# booster_2_01_32U4.net
KiCad netlist of a schematic drawn in EAGLE
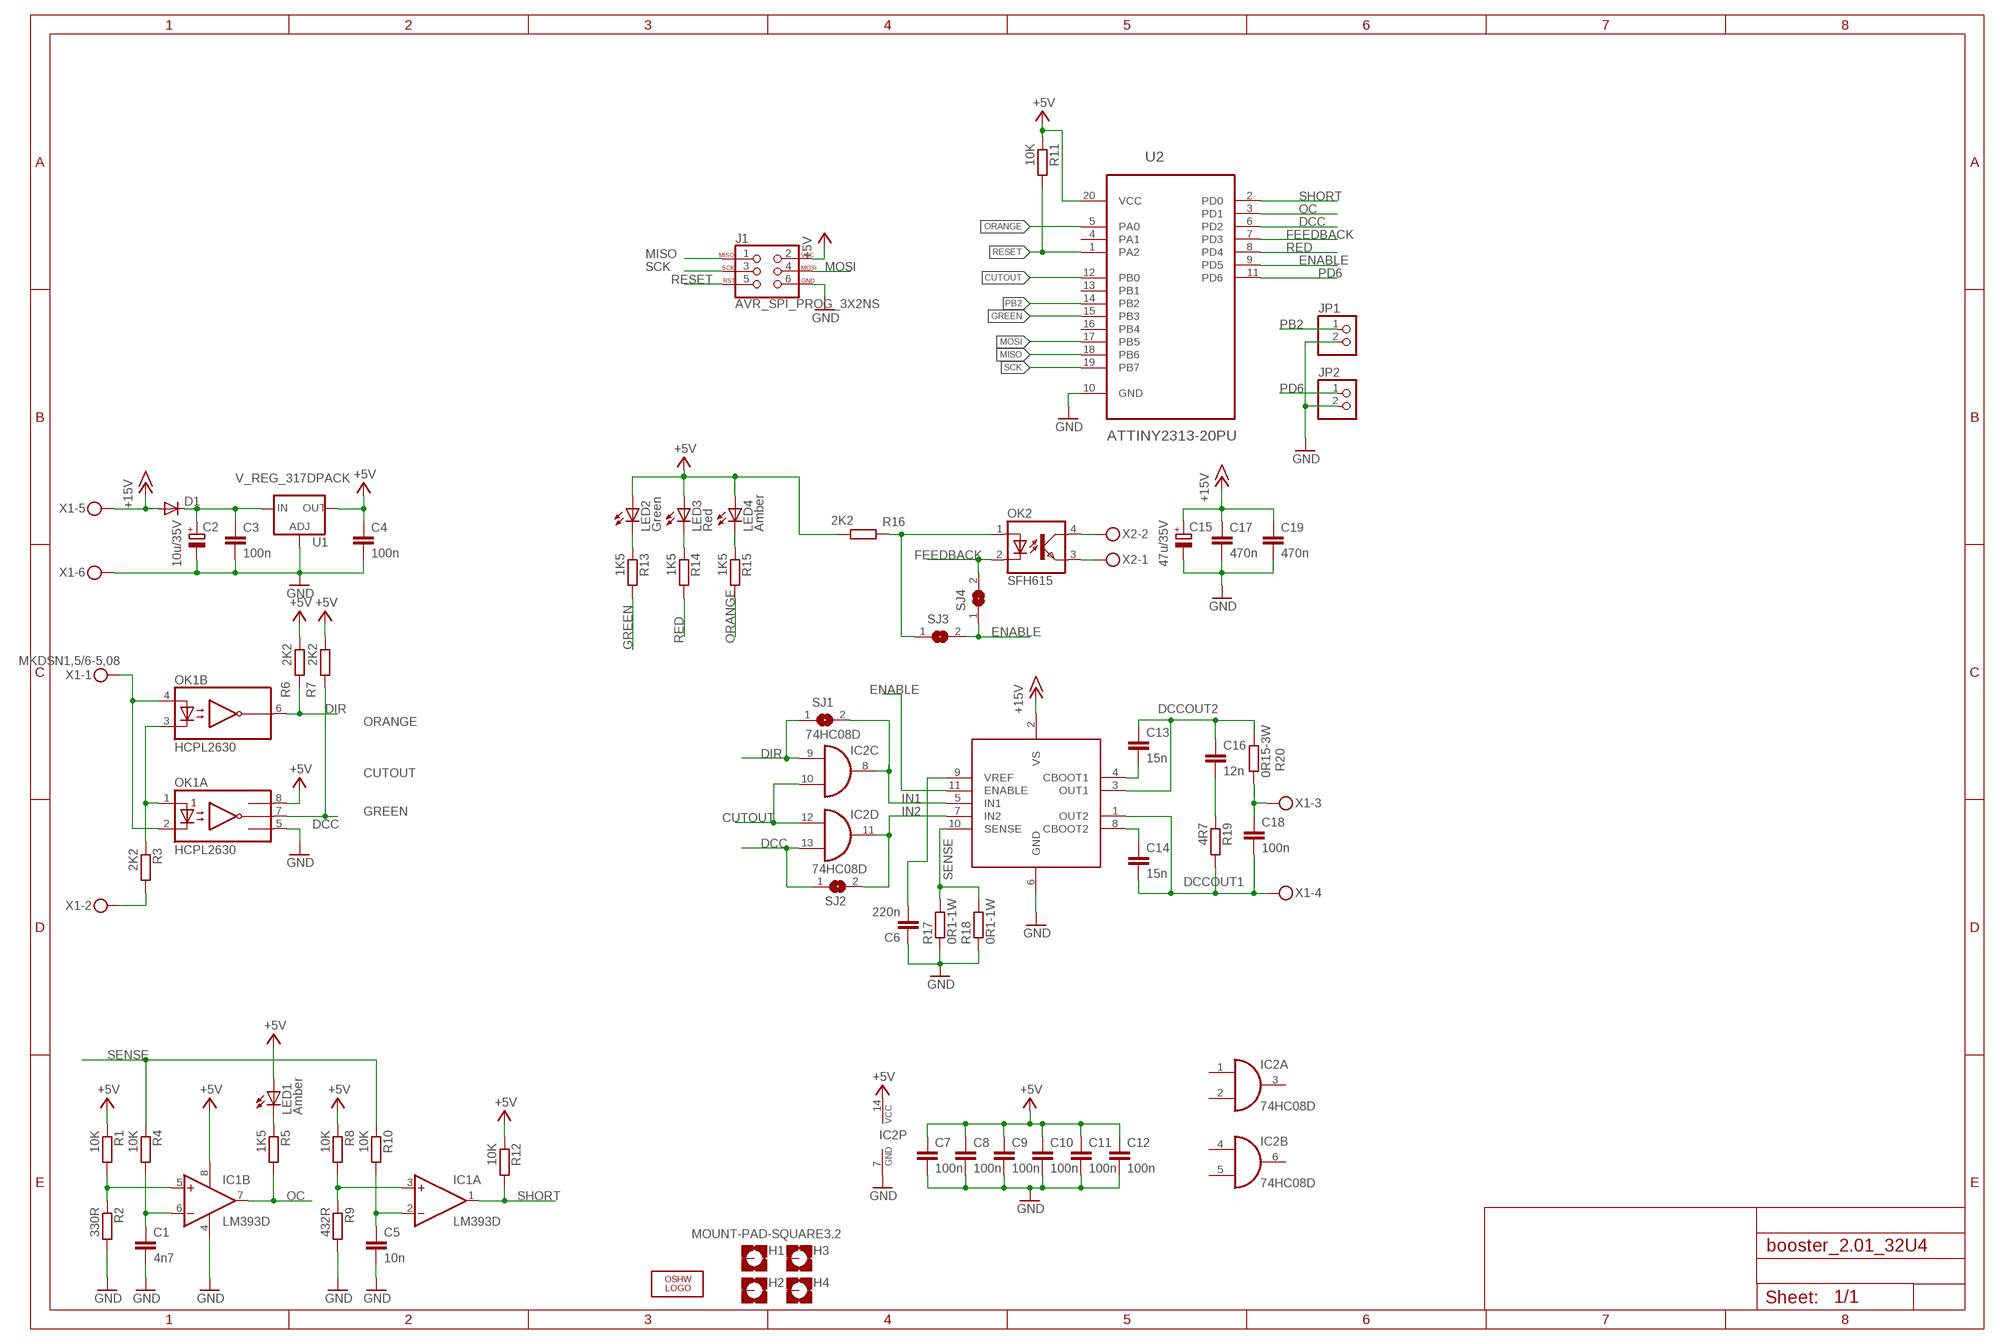
[diagram p0: schematic, sheet 1]

(export (version "E")
  (design (tool "Eeschema 10.0.6"))
  (components
    (comp (ref "C1")
      (value "4n7")
      (footprint "eagle-import:C0805")
      (libsource (lib "eagle-import") (part "C-EUC0805"))
    )
    (comp (ref "C2")
      (value "10u/35V")
      (footprint "eagle-import:E2,5-5")
      (libsource (lib "eagle-import") (part "CPOL-EUE2.5-5"))
    )
    (comp (ref "C3")
      (value "100n")
      (footprint "eagle-import:C0805")
      (libsource (lib "eagle-import") (part "C-EUC0805"))
    )
    (comp (ref "C4")
      (value "100n")
      (footprint "eagle-import:C0805")
      (libsource (lib "eagle-import") (part "C-EUC0805"))
    )
    (comp (ref "C5")
      (value "10n")
      (footprint "eagle-import:C0805")
      (libsource (lib "eagle-import") (part "C-EUC0805"))
    )
    (comp (ref "C6")
      (value "220n")
      (footprint "eagle-import:C0805")
      (libsource (lib "eagle-import") (part "C-EUC0805"))
    )
    (comp (ref "C7")
      (value "100n")
      (footprint "eagle-import:C0805")
      (libsource (lib "eagle-import") (part "C-EUC0805"))
    )
    (comp (ref "C8")
      (value "100n")
      (footprint "eagle-import:C0805")
      (libsource (lib "eagle-import") (part "C-EUC0805"))
    )
    (comp (ref "C9")
      (value "100n")
      (footprint "eagle-import:C0805")
      (libsource (lib "eagle-import") (part "C-EUC0805"))
    )
    (comp (ref "C10")
      (value "100n")
      (footprint "eagle-import:C0805")
      (libsource (lib "eagle-import") (part "C-EUC0805"))
    )
    (comp (ref "C11")
      (value "100n")
      (footprint "eagle-import:C0805")
      (libsource (lib "eagle-import") (part "C-EUC0805"))
    )
    (comp (ref "C12")
      (value "100n")
      (footprint "eagle-import:C0805")
      (libsource (lib "eagle-import") (part "C-EUC0805"))
    )
    (comp (ref "C13")
      (value "15n")
      (footprint "eagle-import:C0805")
      (libsource (lib "eagle-import") (part "C-EUC0805"))
    )
    (comp (ref "C14")
      (value "15n")
      (footprint "eagle-import:C0805")
      (libsource (lib "eagle-import") (part "C-EUC0805"))
    )
    (comp (ref "C15")
      (value "47u/35V")
      (footprint "eagle-import:E2,5-5")
      (libsource (lib "eagle-import") (part "CPOL-EUE2.5-5"))
    )
    (comp (ref "C16")
      (value "12n")
      (footprint "eagle-import:C0805")
      (libsource (lib "eagle-import") (part "C-EUC0805"))
    )
    (comp (ref "C17")
      (value "470n")
      (footprint "eagle-import:C1812")
      (libsource (lib "eagle-import") (part "rcl_334_C-EUC1812"))
    )
    (comp (ref "C18")
      (value "100n")
      (footprint "eagle-import:C0805")
      (libsource (lib "eagle-import") (part "C-EUC0805"))
    )
    (comp (ref "C19")
      (value "470n")
      (footprint "eagle-import:C1812")
      (libsource (lib "eagle-import") (part "rcl_334_C-EUC1812"))
    )
    (comp (ref "D1")
      (value "DIODE-SMB")
      (footprint "eagle-import:SMB")
      (libsource (lib "eagle-import") (part "DIODE-SMB"))
    )
    (comp (ref "H1")
      (value "MOUNT-PAD-SQUARE3.2")
      (footprint "eagle-import:3,2-PAD-SQUARE")
      (libsource (lib "eagle-import") (part "MOUNT-PAD-SQUARE3.2"))
    )
    (comp (ref "H2")
      (value "MOUNT-PAD-SQUARE3.2")
      (footprint "eagle-import:3,2-PAD-SQUARE")
      (libsource (lib "eagle-import") (part "MOUNT-PAD-SQUARE3.2"))
    )
    (comp (ref "H3")
      (value "MOUNT-PAD-SQUARE3.2")
      (footprint "eagle-import:3,2-PAD-SQUARE")
      (libsource (lib "eagle-import") (part "MOUNT-PAD-SQUARE3.2"))
    )
    (comp (ref "H4")
      (value "MOUNT-PAD-SQUARE3.2")
      (footprint "eagle-import:3,2-PAD-SQUARE")
      (libsource (lib "eagle-import") (part "MOUNT-PAD-SQUARE3.2"))
    )
    (comp (ref "IC1")
      (value "LM393D")
      (footprint "eagle-import:SO08")
      (libsource (lib "eagle-import") (part "LM393D"))
    )
    (comp (ref "IC2")
      (value "74HC08D")
      (footprint "eagle-import:SO14")
      (libsource (lib "eagle-import") (part "7408DHC"))
    )
    (comp (ref "J1")
      (value "AVR_SPI_PROG_3X2NS")
      (footprint "eagle-import:2X3-NS")
      (libsource (lib "eagle-import") (part "AVR_SPI_PROG_3X2NS"))
    )
    (comp (ref "JP1")
      (value "PINHD-1X2")
      (footprint "eagle-import:1X02")
      (libsource (lib "eagle-import") (part "PINHD-1X2"))
    )
    (comp (ref "JP2")
      (value "PINHD-1X2")
      (footprint "eagle-import:1X02")
      (libsource (lib "eagle-import") (part "PINHD-1X2"))
    )
    (comp (ref "LED1")
      (value "Amber")
      (footprint "eagle-import:LED3MM")
      (libsource (lib "eagle-import") (part "LED3MM"))
    )
    (comp (ref "LED2")
      (value "Green")
      (footprint "eagle-import:LED3MM")
      (libsource (lib "eagle-import") (part "LED3MM"))
    )
    (comp (ref "LED3")
      (value "Red")
      (footprint "eagle-import:LED3MM")
      (libsource (lib "eagle-import") (part "LED3MM"))
    )
    (comp (ref "LED4")
      (value "Amber")
      (footprint "eagle-import:LED3MM")
      (libsource (lib "eagle-import") (part "LED3MM"))
    )
    (comp (ref "LOGO1")
      (value "OSHW_LOGO_6MILX0200-NT")
      (footprint "eagle-import:OSHW_6X200_NOTEXT")
      (libsource (lib "eagle-import") (part "OSHW_LOGO_6MILX0200-NT"))
    )
    (comp (ref "OK1")
      (value "HCPL2630")
      (footprint "eagle-import:DIL08")
      (fields (field (name "MF") "AGILENT TECHNOLOGIES") (field (name "MPN") "HCPL-2630-000E"))
      (libsource (lib "eagle-import") (part "HCPL2630"))
    )
    (comp (ref "OK2")
      (value "SFH615")
      (footprint "eagle-import:DIL04")
      (fields (field (name "MPN") "SFH615A-2"))
      (libsource (lib "eagle-import") (part "SFH615"))
    )
    (comp (ref "R1")
      (value "10K")
      (footprint "eagle-import:R0805")
      (libsource (lib "eagle-import") (part "R-EU_R0805"))
    )
    (comp (ref "R2")
      (value "330R")
      (footprint "eagle-import:R0805")
      (libsource (lib "eagle-import") (part "R-EU_R0805"))
    )
    (comp (ref "R3")
      (value "2K2")
      (footprint "eagle-import:R0805")
      (libsource (lib "eagle-import") (part "R-EU_R0805"))
    )
    (comp (ref "R4")
      (value "10K")
      (footprint "eagle-import:R0805")
      (libsource (lib "eagle-import") (part "R-EU_R0805"))
    )
    (comp (ref "R5")
      (value "1K5")
      (footprint "eagle-import:R0805")
      (libsource (lib "eagle-import") (part "R-EU_R0805"))
    )
    (comp (ref "R6")
      (value "2K2")
      (footprint "eagle-import:R0805")
      (libsource (lib "eagle-import") (part "R-EU_R0805"))
    )
    (comp (ref "R7")
      (value "2K2")
      (footprint "eagle-import:R0805")
      (libsource (lib "eagle-import") (part "R-EU_R0805"))
    )
    (comp (ref "R8")
      (value "10K")
      (footprint "eagle-import:R0805")
      (libsource (lib "eagle-import") (part "R-EU_R0805"))
    )
    (comp (ref "R9")
      (value "432R")
      (footprint "eagle-import:R0805")
      (libsource (lib "eagle-import") (part "R-EU_R0805"))
    )
    (comp (ref "R10")
      (value "10K")
      (footprint "eagle-import:R0805")
      (libsource (lib "eagle-import") (part "R-EU_R0805"))
    )
    (comp (ref "R11")
      (value "10K")
      (footprint "eagle-import:R0805")
      (libsource (lib "eagle-import") (part "R-EU_R0805"))
    )
    (comp (ref "R12")
      (value "10K")
      (footprint "eagle-import:R0805")
      (libsource (lib "eagle-import") (part "R-EU_R0805"))
    )
    (comp (ref "R13")
      (value "1K5")
      (footprint "eagle-import:R0805")
      (libsource (lib "eagle-import") (part "R-EU_R0805"))
    )
    (comp (ref "R14")
      (value "1K5")
      (footprint "eagle-import:R0805")
      (libsource (lib "eagle-import") (part "R-EU_R0805"))
    )
    (comp (ref "R15")
      (value "1K5")
      (footprint "eagle-import:R0805")
      (libsource (lib "eagle-import") (part "R-EU_R0805"))
    )
    (comp (ref "R16")
      (value "2K2")
      (footprint "eagle-import:R0805")
      (libsource (lib "eagle-import") (part "R-EU_R0805"))
    )
    (comp (ref "R17")
      (value "0R1-1W")
      (footprint "eagle-import:R2512")
      (libsource (lib "eagle-import") (part "rcl_334_R-EU_R2512"))
    )
    (comp (ref "R18")
      (value "0R1-1W")
      (footprint "eagle-import:R2512")
      (libsource (lib "eagle-import") (part "rcl_334_R-EU_R2512"))
    )
    (comp (ref "R19")
      (value "4R7")
      (footprint "eagle-import:R0805")
      (libsource (lib "eagle-import") (part "R-EU_R0805"))
    )
    (comp (ref "R20")
      (value "0R15-3W")
      (footprint "eagle-import:P0817V")
      (libsource (lib "eagle-import") (part "rcl_334_R-EU_0817/7V"))
    )
    (comp (ref "SJ1") (value "SJ") (footprint "eagle-import:SJ") (libsource (lib "eagle-import") (part "SJ")))
    (comp (ref "SJ2") (value "SJ") (footprint "eagle-import:SJ") (libsource (lib "eagle-import") (part "SJ")))
    (comp (ref "SJ3") (value "SJ") (footprint "eagle-import:SJ") (libsource (lib "eagle-import") (part "SJ")))
    (comp (ref "SJ4") (value "SJ") (footprint "eagle-import:SJ") (libsource (lib "eagle-import") (part "SJ")))
    (comp (ref "U1")
      (value "V_REG_317DPACK")
      (footprint "eagle-import:V-REG_DPACK")
      (libsource (lib "eagle-import") (part "V_REG_317DPACK"))
    )
    (comp (ref "U2")
      (value "ATTINY2313-20PU")
      (footprint "eagle-import:DIP254P762X533-20")
      (libsource (lib "eagle-import") (part "ATTINY2313-20PU"))
    )
    (comp (ref "U3")
      (value "L6203")
      (footprint "eagle-import:ZIP_11")
      (fields (field (name "MANUFACTURER") "STM"))
      (libsource (lib "eagle-import") (part "L6203"))
    )
    (comp (ref "X1")
      (value "MKDSN1,5/6-5,08")
      (footprint "eagle-import:MKDSN1,5_6-5,08")
      (libsource (lib "eagle-import") (part "MKDSN1,5/6-5,08"))
    )
    (comp (ref "X2")
      (value "MKDSN1,5/2-5,08")
      (footprint "eagle-import:MKDSN1,5_2-5,08")
      (libsource (lib "eagle-import") (part "MKDSN1,5/2-5,08"))
    )
  )
  (nets
    (net (code "1") (name "+5V") (class "Default")
      (node (ref "C10") (pin "1") (pinfunction "1_1") (pintype "passive"))
      (node (ref "C11") (pin "1") (pinfunction "1_1") (pintype "passive"))
      (node (ref "C12") (pin "1") (pinfunction "1_1") (pintype "passive"))
      (node (ref "C4") (pin "1") (pinfunction "1_1") (pintype "passive"))
      (node (ref "C7") (pin "1") (pinfunction "1_1") (pintype "passive"))
      (node (ref "C8") (pin "1") (pinfunction "1_1") (pintype "passive"))
      (node (ref "C9") (pin "1") (pinfunction "1_1") (pintype "passive"))
      (node (ref "IC1") (pin "8") (pinfunction "V+_8") (pintype "power_in"))
      (node (ref "IC2") (pin "14") (pinfunction "VCC_14") (pintype "power_in"))
      (node (ref "J1") (pin "2") (pinfunction "2_2") (pintype "passive"))
      (node (ref "LED1") (pin "A") (pinfunction "A_A") (pintype "passive"))
      (node (ref "LED2") (pin "A") (pinfunction "A_A") (pintype "passive"))
      (node (ref "LED3") (pin "A") (pinfunction "A_A") (pintype "passive"))
      (node (ref "LED4") (pin "A") (pinfunction "A_A") (pintype "passive"))
      (node (ref "OK1") (pin "8") (pinfunction "VCC_8") (pintype "passive"))
      (node (ref "R1") (pin "1") (pinfunction "1_1") (pintype "passive"))
      (node (ref "R11") (pin "1") (pinfunction "1_1") (pintype "passive"))
      (node (ref "R12") (pin "1") (pinfunction "1_1") (pintype "passive"))
      (node (ref "R16") (pin "1") (pinfunction "1_1") (pintype "passive"))
      (node (ref "R6") (pin "1") (pinfunction "1_1") (pintype "passive"))
      (node (ref "R7") (pin "1") (pinfunction "1_1") (pintype "passive"))
      (node (ref "R8") (pin "1") (pinfunction "1_1") (pintype "passive"))
      (node (ref "U1") (pin "4") (pinfunction "OUT_4") (pintype "output"))
      (node (ref "U2") (pin "20") (pinfunction "VCC_20") (pintype "power_in"))
    )
    (net (code "2") (name "+15V") (class "Default")
      (node (ref "C15") (pin "+") (pinfunction "+_+") (pintype "passive"))
      (node (ref "C17") (pin "1") (pinfunction "1_1") (pintype "passive"))
      (node (ref "C19") (pin "1") (pinfunction "1_1") (pintype "passive"))
      (node (ref "D1") (pin "A") (pinfunction "A_A") (pintype "passive"))
      (node (ref "U3") (pin "2") (pinfunction "VS_2") (pintype "power_in"))
      (node (ref "X1") (pin "5") (pinfunction "KL_5") (pintype "passive"))
    )
    (net (code "3") (name "/DCC") (class "Default")
      (node (ref "IC2") (pin "13") (pinfunction "I1_13") (pintype "input"))
      (node (ref "OK1") (pin "7") (pinfunction "VO1_7") (pintype "passive"))
      (node (ref "R7") (pin "2") (pinfunction "2_2") (pintype "passive"))
      (node (ref "SJ2") (pin "1") (pinfunction "1_1") (pintype "passive"))
      (node (ref "U2") (pin "6") (pinfunction "PD2_6") (pintype "bidirectional"))
    )
    (net (code "4") (name "/DCCOUT1") (class "Default")
      (node (ref "C14") (pin "2") (pinfunction "2_2") (pintype "passive"))
      (node (ref "C18") (pin "2") (pinfunction "2_2") (pintype "passive"))
      (node (ref "R19") (pin "2") (pinfunction "2_2") (pintype "passive"))
      (node (ref "U3") (pin "1") (pinfunction "OUT2_1") (pintype "output"))
      (node (ref "X1") (pin "4") (pinfunction "KL_4") (pintype "passive"))
    )
    (net (code "5") (name "/DCCOUT2") (class "Default")
      (node (ref "C13") (pin "1") (pinfunction "1_1") (pintype "passive"))
      (node (ref "C16") (pin "1") (pinfunction "1_1") (pintype "passive"))
      (node (ref "R20") (pin "2") (pinfunction "2_2") (pintype "passive"))
      (node (ref "U3") (pin "3") (pinfunction "OUT1_3") (pintype "output"))
    )
    (net (code "6") (name "/DIR") (class "Default")
      (node (ref "IC2") (pin "9") (pinfunction "I0_9") (pintype "input"))
      (node (ref "OK1") (pin "6") (pinfunction "VO2_6") (pintype "passive"))
      (node (ref "R6") (pin "2") (pinfunction "2_2") (pintype "passive"))
      (node (ref "SJ1") (pin "1") (pinfunction "1_1") (pintype "passive"))
    )
    (net (code "7") (name "/ENABLE") (class "Default")
      (node (ref "SJ3") (pin "2") (pinfunction "2_2") (pintype "passive"))
      (node (ref "SJ4") (pin "1") (pinfunction "1_1") (pintype "passive"))
      (node (ref "U2") (pin "9") (pinfunction "PD5_9") (pintype "bidirectional"))
      (node (ref "U3") (pin "11") (pinfunction "ENABLE_11") (pintype "input"))
    )
    (net (code "8") (name "/FEEDBACK") (class "Default")
      (node (ref "OK2") (pin "2") (pinfunction "C_2") (pintype "passive"))
      (node (ref "SJ4") (pin "2") (pinfunction "2_2") (pintype "passive"))
      (node (ref "U2") (pin "7") (pinfunction "PD3_7") (pintype "bidirectional"))
    )
    (net (code "9") (name "/IN1") (class "Default")
      (node (ref "IC2") (pin "8") (pinfunction "O_8") (pintype "output"))
      (node (ref "SJ1") (pin "2") (pinfunction "2_2") (pintype "passive"))
      (node (ref "U3") (pin "5") (pinfunction "IN1_5") (pintype "input"))
    )
    (net (code "10") (name "/IN2") (class "Default")
      (node (ref "IC2") (pin "11") (pinfunction "O_11") (pintype "output"))
      (node (ref "SJ2") (pin "2") (pinfunction "2_2") (pintype "passive"))
      (node (ref "U3") (pin "7") (pinfunction "IN2_7") (pintype "input"))
    )
    (net (code "11") (name "/OC") (class "Default")
      (node (ref "IC1") (pin "7") (pinfunction "OUT_7") (pintype "output"))
      (node (ref "R5") (pin "2") (pinfunction "2_2") (pintype "passive"))
      (node (ref "U2") (pin "3") (pinfunction "PD1_3") (pintype "bidirectional"))
    )
    (net (code "12") (name "/PD6") (class "Default")
      (node (ref "JP2") (pin "1") (pinfunction "1_1") (pintype "passive"))
      (node (ref "U2") (pin "11") (pinfunction "PD6_11") (pintype "bidirectional"))
    )
    (net (code "13") (name "/RED") (class "Default")
      (node (ref "R14") (pin "2") (pinfunction "2_2") (pintype "passive"))
      (node (ref "U2") (pin "8") (pinfunction "PD4_8") (pintype "bidirectional"))
    )
    (net (code "14") (name "/SENSE") (class "Default")
      (node (ref "R10") (pin "1") (pinfunction "1_1") (pintype "passive"))
      (node (ref "R17") (pin "2") (pinfunction "2_2") (pintype "passive"))
      (node (ref "R18") (pin "2") (pinfunction "2_2") (pintype "passive"))
      (node (ref "R4") (pin "1") (pinfunction "1_1") (pintype "passive"))
      (node (ref "U3") (pin "10") (pinfunction "SENSE_10") (pintype "input"))
    )
    (net (code "15") (name "/SHORT") (class "Default")
      (node (ref "IC1") (pin "1") (pinfunction "OUT_1") (pintype "output"))
      (node (ref "R12") (pin "2") (pinfunction "2_2") (pintype "passive"))
      (node (ref "U2") (pin "2") (pinfunction "PD0_2") (pintype "bidirectional"))
    )
    (net (code "16") (name "CUTOUT") (class "Default")
      (node (ref "IC2") (pin "10") (pinfunction "I1_10") (pintype "input"))
      (node (ref "IC2") (pin "12") (pinfunction "I0_12") (pintype "input"))
      (node (ref "U2") (pin "12") (pinfunction "PB0_12") (pintype "bidirectional"))
    )
    (net (code "17") (name "GND") (class "Default")
      (node (ref "C1") (pin "2") (pinfunction "2_2") (pintype "passive"))
      (node (ref "C10") (pin "2") (pinfunction "2_2") (pintype "passive"))
      (node (ref "C11") (pin "2") (pinfunction "2_2") (pintype "passive"))
      (node (ref "C12") (pin "2") (pinfunction "2_2") (pintype "passive"))
      (node (ref "C15") (pin "-") (pinfunction "-_-") (pintype "passive"))
      (node (ref "C17") (pin "2") (pinfunction "2_2") (pintype "passive"))
      (node (ref "C19") (pin "2") (pinfunction "2_2") (pintype "passive"))
      (node (ref "C2") (pin "-") (pinfunction "-_-") (pintype "passive"))
      (node (ref "C3") (pin "2") (pinfunction "2_2") (pintype "passive"))
      (node (ref "C4") (pin "2") (pinfunction "2_2") (pintype "passive"))
      (node (ref "C5") (pin "2") (pinfunction "2_2") (pintype "passive"))
      (node (ref "C6") (pin "1") (pinfunction "1_1") (pintype "passive"))
      (node (ref "C7") (pin "2") (pinfunction "2_2") (pintype "passive"))
      (node (ref "C8") (pin "2") (pinfunction "2_2") (pintype "passive"))
      (node (ref "C9") (pin "2") (pinfunction "2_2") (pintype "passive"))
      (node (ref "IC1") (pin "4") (pinfunction "V-_4") (pintype "power_in"))
      (node (ref "IC2") (pin "7") (pinfunction "GND_7") (pintype "power_in"))
      (node (ref "J1") (pin "6") (pinfunction "6_6") (pintype "passive"))
      (node (ref "JP1") (pin "2") (pinfunction "2_2") (pintype "passive"))
      (node (ref "JP2") (pin "2") (pinfunction "2_2") (pintype "passive"))
      (node (ref "OK1") (pin "5") (pinfunction "GND_5") (pintype "passive"))
      (node (ref "R17") (pin "1") (pinfunction "1_1") (pintype "passive"))
      (node (ref "R18") (pin "1") (pinfunction "1_1") (pintype "passive"))
      (node (ref "R2") (pin "2") (pinfunction "2_2") (pintype "passive"))
      (node (ref "R9") (pin "2") (pinfunction "2_2") (pintype "passive"))
      (node (ref "U1") (pin "1") (pinfunction "ADJ_1") (pintype "input"))
      (node (ref "U2") (pin "10") (pinfunction "GND_10") (pintype "passive"))
      (node (ref "U3") (pin "6") (pinfunction "GND_6") (pintype "passive"))
      (node (ref "X1") (pin "6") (pinfunction "KL_6") (pintype "passive"))
    )
    (net (code "18") (name "GREEN") (class "Default")
      (node (ref "R13") (pin "2") (pinfunction "2_2") (pintype "passive"))
      (node (ref "U2") (pin "15") (pinfunction "PB3_15") (pintype "bidirectional"))
    )
    (net (code "19") (name "MISO") (class "Default")
      (node (ref "J1") (pin "1") (pinfunction "1_1") (pintype "passive"))
      (node (ref "U2") (pin "18") (pinfunction "PB6_18") (pintype "bidirectional"))
    )
    (net (code "20") (name "MOSI") (class "Default")
      (node (ref "J1") (pin "4") (pinfunction "4_4") (pintype "passive"))
      (node (ref "U2") (pin "17") (pinfunction "PB5_17") (pintype "bidirectional"))
    )
    (net (code "21") (name "Net-(C16-Pad2)") (class "Default")
      (node (ref "C16") (pin "2") (pinfunction "2_2") (pintype "passive"))
      (node (ref "R19") (pin "1") (pinfunction "1_1") (pintype "passive"))
    )
    (net (code "22") (name "Net-(IC1A-+IN)") (class "Default")
      (node (ref "IC1") (pin "3") (pinfunction "+IN_3") (pintype "input"))
      (node (ref "R8") (pin "2") (pinfunction "2_2") (pintype "passive"))
      (node (ref "R9") (pin "1") (pinfunction "1_1") (pintype "passive"))
    )
    (net (code "23") (name "Net-(IC1A--IN)") (class "Default")
      (node (ref "C5") (pin "1") (pinfunction "1_1") (pintype "passive"))
      (node (ref "IC1") (pin "2") (pinfunction "-IN_2") (pintype "input"))
      (node (ref "R10") (pin "2") (pinfunction "2_2") (pintype "passive"))
    )
    (net (code "24") (name "Net-(IC1B-+IN)") (class "Default")
      (node (ref "IC1") (pin "5") (pinfunction "+IN_5") (pintype "input"))
      (node (ref "R1") (pin "2") (pinfunction "2_2") (pintype "passive"))
      (node (ref "R2") (pin "1") (pinfunction "1_1") (pintype "passive"))
    )
    (net (code "25") (name "Net-(IC1B--IN)") (class "Default")
      (node (ref "C1") (pin "1") (pinfunction "1_1") (pintype "passive"))
      (node (ref "IC1") (pin "6") (pinfunction "-IN_6") (pintype "input"))
      (node (ref "R4") (pin "2") (pinfunction "2_2") (pintype "passive"))
    )
    (net (code "26") (name "Net-(LED1-C)") (class "Default")
      (node (ref "LED1") (pin "K") (pinfunction "C_K") (pintype "passive"))
      (node (ref "R5") (pin "1") (pinfunction "1_1") (pintype "passive"))
    )
    (net (code "27") (name "Net-(LED2-C)") (class "Default")
      (node (ref "LED2") (pin "K") (pinfunction "C_K") (pintype "passive"))
      (node (ref "R13") (pin "1") (pinfunction "1_1") (pintype "passive"))
    )
    (net (code "28") (name "Net-(LED3-C)") (class "Default")
      (node (ref "LED3") (pin "K") (pinfunction "C_K") (pintype "passive"))
      (node (ref "R14") (pin "1") (pinfunction "1_1") (pintype "passive"))
    )
    (net (code "29") (name "Net-(LED4-C)") (class "Default")
      (node (ref "LED4") (pin "K") (pinfunction "C_K") (pintype "passive"))
      (node (ref "R15") (pin "1") (pinfunction "1_1") (pintype "passive"))
    )
    (net (code "30") (name "Net-(OK1A-A1)") (class "Default")
      (node (ref "OK1") (pin "1") (pinfunction "A1_1") (pintype "passive"))
      (node (ref "OK1") (pin "3") (pinfunction "C2_3") (pintype "passive"))
      (node (ref "R3") (pin "1") (pinfunction "1_1") (pintype "passive"))
    )
    (net (code "31") (name "Net-(OK1A-C1)") (class "Default")
      (node (ref "OK1") (pin "2") (pinfunction "C1_2") (pintype "passive"))
      (node (ref "OK1") (pin "4") (pinfunction "A2_4") (pintype "passive"))
      (node (ref "X1") (pin "1") (pinfunction "KL_1") (pintype "passive"))
    )
    (net (code "32") (name "Net-(OK2-A)") (class "Default")
      (node (ref "OK2") (pin "1") (pinfunction "A_1") (pintype "passive"))
      (node (ref "R16") (pin "2") (pinfunction "2_2") (pintype "passive"))
      (node (ref "SJ3") (pin "1") (pinfunction "1_1") (pintype "passive"))
    )
    (net (code "33") (name "Net-(OK2-COL)") (class "Default")
      (node (ref "OK2") (pin "4") (pinfunction "COL_4") (pintype "passive"))
      (node (ref "X2") (pin "2") (pinfunction "KL_2") (pintype "passive"))
    )
    (net (code "34") (name "Net-(OK2-EMIT)") (class "Default")
      (node (ref "OK2") (pin "3") (pinfunction "EMIT_3") (pintype "passive"))
      (node (ref "X2") (pin "1") (pinfunction "KL_1") (pintype "passive"))
    )
    (net (code "35") (name "Net-(U1-IN)") (class "Default")
      (node (ref "C2") (pin "+") (pinfunction "+_+") (pintype "passive"))
      (node (ref "C3") (pin "1") (pinfunction "1_1") (pintype "passive"))
      (node (ref "D1") (pin "C") (pinfunction "C_C") (pintype "passive"))
      (node (ref "U1") (pin "3") (pinfunction "IN_3") (pintype "input"))
    )
    (net (code "36") (name "Net-(U3-CBOOT1)") (class "Default")
      (node (ref "C13") (pin "2") (pinfunction "2_2") (pintype "passive"))
      (node (ref "U3") (pin "4") (pinfunction "CBOOT1_4") (pintype "output"))
    )
    (net (code "37") (name "Net-(U3-CBOOT2)") (class "Default")
      (node (ref "C14") (pin "1") (pinfunction "1_1") (pintype "passive"))
      (node (ref "U3") (pin "8") (pinfunction "CBOOT2_8") (pintype "output"))
    )
    (net (code "38") (name "Net-(U3-VREF)") (class "Default")
      (node (ref "C6") (pin "2") (pinfunction "2_2") (pintype "passive"))
      (node (ref "U3") (pin "9") (pinfunction "VREF_9") (pintype "output"))
    )
    (net (code "39") (name "Net-(X1B-KL)") (class "Default")
      (node (ref "R3") (pin "2") (pinfunction "2_2") (pintype "passive"))
      (node (ref "X1") (pin "2") (pinfunction "KL_2") (pintype "passive"))
    )
    (net (code "40") (name "Net-(X1C-KL)") (class "Default")
      (node (ref "C18") (pin "1") (pinfunction "1_1") (pintype "passive"))
      (node (ref "R20") (pin "1") (pinfunction "1_1") (pintype "passive"))
      (node (ref "X1") (pin "3") (pinfunction "KL_3") (pintype "passive"))
    )
    (net (code "41") (name "ORANGE") (class "Default")
      (node (ref "R15") (pin "2") (pinfunction "2_2") (pintype "passive"))
      (node (ref "U2") (pin "5") (pinfunction "PA0_5") (pintype "bidirectional"))
    )
    (net (code "42") (name "PB2") (class "Default")
      (node (ref "JP1") (pin "1") (pinfunction "1_1") (pintype "passive"))
      (node (ref "U2") (pin "14") (pinfunction "PB2_14") (pintype "bidirectional"))
    )
    (net (code "43") (name "RESET") (class "Default")
      (node (ref "J1") (pin "5") (pinfunction "5_5") (pintype "passive"))
      (node (ref "R11") (pin "2") (pinfunction "2_2") (pintype "passive"))
      (node (ref "U2") (pin "1") (pinfunction "PA2_1") (pintype "bidirectional"))
    )
    (net (code "44") (name "SCK") (class "Default")
      (node (ref "J1") (pin "3") (pinfunction "3_3") (pintype "passive"))
      (node (ref "U2") (pin "19") (pinfunction "PB7_19") (pintype "bidirectional"))
    )
    (net (code "45") (name "unconnected-(H1-MOUNT-PadB3,2)") (class "Default")
      (node (ref "H1") (pin "B3,2") (pinfunction "MOUNT_B3,2") (pintype "passive"))
    )
    (net (code "46") (name "unconnected-(H2-MOUNT-PadB3,2)") (class "Default")
      (node (ref "H2") (pin "B3,2") (pinfunction "MOUNT_B3,2") (pintype "passive"))
    )
    (net (code "47") (name "unconnected-(H3-MOUNT-PadB3,2)") (class "Default")
      (node (ref "H3") (pin "B3,2") (pinfunction "MOUNT_B3,2") (pintype "passive"))
    )
    (net (code "48") (name "unconnected-(H4-MOUNT-PadB3,2)") (class "Default")
      (node (ref "H4") (pin "B3,2") (pinfunction "MOUNT_B3,2") (pintype "passive"))
    )
    (net (code "49") (name "unconnected-(IC2A-I0-Pad1)") (class "Default")
      (node (ref "IC2") (pin "1") (pinfunction "I0_1") (pintype "input"))
    )
    (net (code "50") (name "unconnected-(IC2A-I1-Pad2)") (class "Default")
      (node (ref "IC2") (pin "2") (pinfunction "I1_2") (pintype "input"))
    )
    (net (code "51") (name "unconnected-(IC2A-O-Pad3)") (class "Default")
      (node (ref "IC2") (pin "3") (pinfunction "O_3") (pintype "output"))
    )
    (net (code "52") (name "unconnected-(IC2B-I0-Pad4)") (class "Default")
      (node (ref "IC2") (pin "4") (pinfunction "I0_4") (pintype "input"))
    )
    (net (code "53") (name "unconnected-(IC2B-I1-Pad5)") (class "Default")
      (node (ref "IC2") (pin "5") (pinfunction "I1_5") (pintype "input"))
    )
    (net (code "54") (name "unconnected-(IC2B-O-Pad6)") (class "Default")
      (node (ref "IC2") (pin "6") (pinfunction "O_6") (pintype "output"))
    )
    (net (code "55") (name "unconnected-(U2-PA1-Pad4)") (class "Default")
      (node (ref "U2") (pin "4") (pinfunction "PA1_4") (pintype "bidirectional"))
    )
    (net (code "56") (name "unconnected-(U2-PB1-Pad13)") (class "Default")
      (node (ref "U2") (pin "13") (pinfunction "PB1_13") (pintype "bidirectional"))
    )
    (net (code "57") (name "unconnected-(U2-PB4-Pad16)") (class "Default")
      (node (ref "U2") (pin "16") (pinfunction "PB4_16") (pintype "bidirectional"))
    )
  )
)
